# AnalogPart.net
KiCad netlist of a schematic drawn in Altium Designer
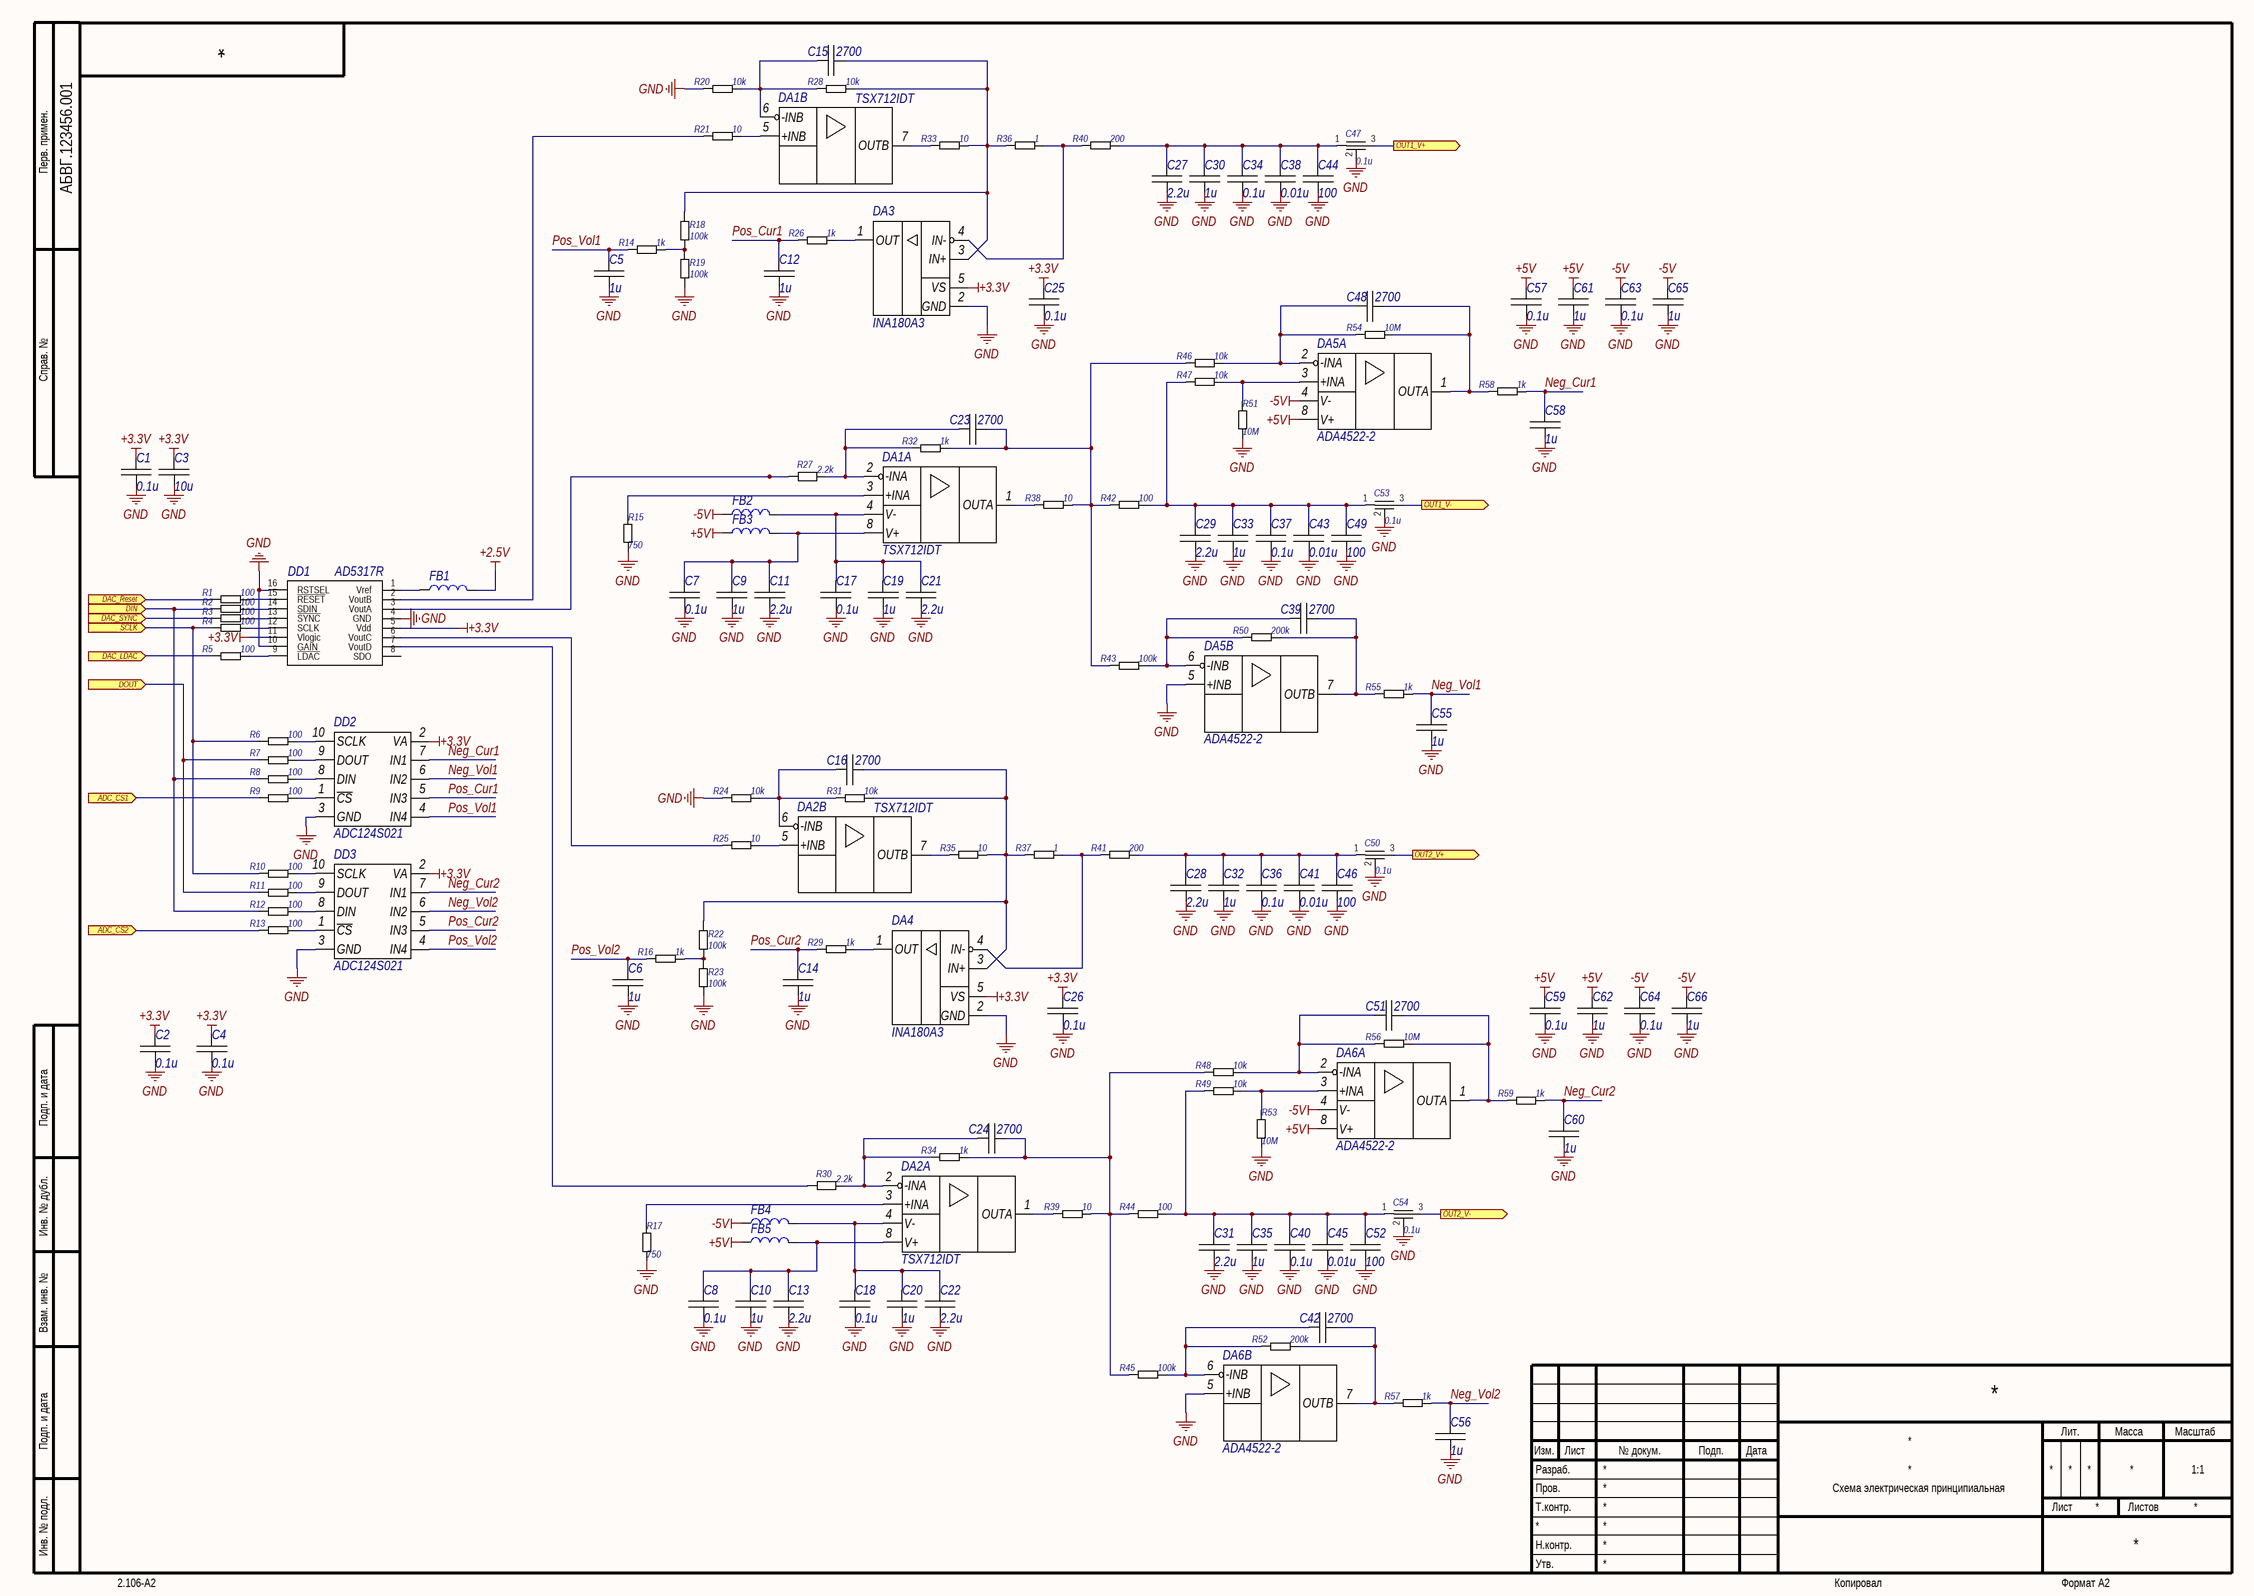
[diagram p0: AnalogPart.SchDoc]

(export (version "E")
  (design (tool "Eeschema 10.0.6"))
  (components
    (comp (ref "C1")
      (value "0.1u")
      (footprint "C0603")
      (libsource (lib "ComLib") (part "Capacitor Ceramic SMD"))
    )
    (comp (ref "C2")
      (value "0.1u")
      (footprint "C0603")
      (libsource (lib "ComLib") (part "Capacitor Ceramic SMD"))
    )
    (comp (ref "C3")
      (value "10u")
      (footprint "C0805")
      (libsource (lib "ComLib") (part "Capacitor Ceramic SMD"))
    )
    (comp (ref "C4")
      (value "0.1u")
      (footprint "C0603")
      (libsource (lib "ComLib") (part "Capacitor Ceramic SMD"))
    )
    (comp (ref "C5")
      (value "1u")
      (footprint "C0805")
      (libsource (lib "ComLib") (part "Capacitor Ceramic SMD"))
    )
    (comp (ref "C6")
      (value "1u")
      (footprint "C0805")
      (libsource (lib "ComLib") (part "Capacitor Ceramic SMD"))
    )
    (comp (ref "C7")
      (value "0.1u")
      (footprint "C0603")
      (libsource (lib "ComLib") (part "Capacitor Ceramic SMD"))
    )
    (comp (ref "C8")
      (value "0.1u")
      (footprint "C0603")
      (libsource (lib "ComLib") (part "Capacitor Ceramic SMD"))
    )
    (comp (ref "C9")
      (value "1u")
      (footprint "C0805")
      (libsource (lib "ComLib") (part "Capacitor Ceramic SMD"))
    )
    (comp (ref "C10")
      (value "1u")
      (footprint "C0805")
      (libsource (lib "ComLib") (part "Capacitor Ceramic SMD"))
    )
    (comp (ref "C11")
      (value "2.2u")
      (footprint "C0805")
      (libsource (lib "ComLib") (part "Capacitor Ceramic SMD"))
    )
    (comp (ref "C12")
      (value "1u")
      (footprint "C0805")
      (libsource (lib "ComLib") (part "Capacitor Ceramic SMD"))
    )
    (comp (ref "C13")
      (value "2.2u")
      (footprint "C0805")
      (libsource (lib "ComLib") (part "Capacitor Ceramic SMD"))
    )
    (comp (ref "C14")
      (value "1u")
      (footprint "C0805")
      (libsource (lib "ComLib") (part "Capacitor Ceramic SMD"))
    )
    (comp (ref "C15")
      (value "2700")
      (footprint "C0805")
      (libsource (lib "ComLib") (part "Capacitor Ceramic SMD"))
    )
    (comp (ref "C16")
      (value "2700")
      (footprint "C0805")
      (libsource (lib "ComLib") (part "Capacitor Ceramic SMD"))
    )
    (comp (ref "C17")
      (value "0.1u")
      (footprint "C0603")
      (libsource (lib "ComLib") (part "Capacitor Ceramic SMD"))
    )
    (comp (ref "C18")
      (value "0.1u")
      (footprint "C0603")
      (libsource (lib "ComLib") (part "Capacitor Ceramic SMD"))
    )
    (comp (ref "C19")
      (value "1u")
      (footprint "C0805")
      (libsource (lib "ComLib") (part "Capacitor Ceramic SMD"))
    )
    (comp (ref "C20")
      (value "1u")
      (footprint "C0805")
      (libsource (lib "ComLib") (part "Capacitor Ceramic SMD"))
    )
    (comp (ref "C21")
      (value "2.2u")
      (footprint "C0805")
      (libsource (lib "ComLib") (part "Capacitor Ceramic SMD"))
    )
    (comp (ref "C22")
      (value "2.2u")
      (footprint "C0805")
      (libsource (lib "ComLib") (part "Capacitor Ceramic SMD"))
    )
    (comp (ref "C23")
      (value "2700")
      (footprint "C0805")
      (libsource (lib "ComLib") (part "Capacitor Ceramic SMD"))
    )
    (comp (ref "C24")
      (value "2700")
      (footprint "C0805")
      (libsource (lib "ComLib") (part "Capacitor Ceramic SMD"))
    )
    (comp (ref "C25")
      (value "0.1u")
      (footprint "C0603")
      (libsource (lib "ComLib") (part "Capacitor Ceramic SMD"))
    )
    (comp (ref "C26")
      (value "0.1u")
      (footprint "C0603")
      (libsource (lib "ComLib") (part "Capacitor Ceramic SMD"))
    )
    (comp (ref "C27")
      (value "2.2u")
      (footprint "C0805")
      (libsource (lib "ComLib") (part "Capacitor Ceramic SMD"))
    )
    (comp (ref "C28")
      (value "2.2u")
      (footprint "C0805")
      (libsource (lib "ComLib") (part "Capacitor Ceramic SMD"))
    )
    (comp (ref "C29")
      (value "2.2u")
      (footprint "C0805")
      (libsource (lib "ComLib") (part "Capacitor Ceramic SMD"))
    )
    (comp (ref "C30")
      (value "1u")
      (footprint "C0805")
      (libsource (lib "ComLib") (part "Capacitor Ceramic SMD"))
    )
    (comp (ref "C31")
      (value "2.2u")
      (footprint "C0805")
      (libsource (lib "ComLib") (part "Capacitor Ceramic SMD"))
    )
    (comp (ref "C32")
      (value "1u")
      (footprint "C0805")
      (libsource (lib "ComLib") (part "Capacitor Ceramic SMD"))
    )
    (comp (ref "C33")
      (value "1u")
      (footprint "C0805")
      (libsource (lib "ComLib") (part "Capacitor Ceramic SMD"))
    )
    (comp (ref "C34")
      (value "0.1u")
      (footprint "C0805")
      (libsource (lib "ComLib") (part "Capacitor Ceramic SMD"))
    )
    (comp (ref "C35")
      (value "1u")
      (footprint "C0805")
      (libsource (lib "ComLib") (part "Capacitor Ceramic SMD"))
    )
    (comp (ref "C36")
      (value "0.1u")
      (footprint "C0805")
      (libsource (lib "ComLib") (part "Capacitor Ceramic SMD"))
    )
    (comp (ref "C37")
      (value "0.1u")
      (footprint "C0805")
      (libsource (lib "ComLib") (part "Capacitor Ceramic SMD"))
    )
    (comp (ref "C38")
      (value "0.01u")
      (footprint "C0805")
      (libsource (lib "ComLib") (part "Capacitor Ceramic SMD"))
    )
    (comp (ref "C39")
      (value "2700")
      (footprint "C0805")
      (libsource (lib "ComLib") (part "Capacitor Ceramic SMD"))
    )
    (comp (ref "C40")
      (value "0.1u")
      (footprint "C0805")
      (libsource (lib "ComLib") (part "Capacitor Ceramic SMD"))
    )
    (comp (ref "C41")
      (value "0.01u")
      (footprint "C0805")
      (libsource (lib "ComLib") (part "Capacitor Ceramic SMD"))
    )
    (comp (ref "C42")
      (value "2700")
      (footprint "C0805")
      (libsource (lib "ComLib") (part "Capacitor Ceramic SMD"))
    )
    (comp (ref "C43")
      (value "0.01u")
      (footprint "C0805")
      (libsource (lib "ComLib") (part "Capacitor Ceramic SMD"))
    )
    (comp (ref "C44")
      (value "100")
      (footprint "C0805")
      (libsource (lib "ComLib") (part "Capacitor Ceramic SMD"))
    )
    (comp (ref "C45")
      (value "0.01u")
      (footprint "C0805")
      (libsource (lib "ComLib") (part "Capacitor Ceramic SMD"))
    )
    (comp (ref "C46")
      (value "100")
      (footprint "C0805")
      (libsource (lib "ComLib") (part "Capacitor Ceramic SMD"))
    )
    (comp (ref "C47") (value "0.1u") (footprint "T0805") (libsource (lib "ComLib") (part "Cap 3 terminal")))
    (comp (ref "C48")
      (value "2700")
      (footprint "C0805")
      (libsource (lib "ComLib") (part "Capacitor Ceramic SMD"))
    )
    (comp (ref "C49")
      (value "100")
      (footprint "C0805")
      (libsource (lib "ComLib") (part "Capacitor Ceramic SMD"))
    )
    (comp (ref "C50") (value "0.1u") (footprint "T0805") (libsource (lib "ComLib") (part "Cap 3 terminal")))
    (comp (ref "C51")
      (value "2700")
      (footprint "C0805")
      (libsource (lib "ComLib") (part "Capacitor Ceramic SMD"))
    )
    (comp (ref "C52")
      (value "100")
      (footprint "C0805")
      (libsource (lib "ComLib") (part "Capacitor Ceramic SMD"))
    )
    (comp (ref "C53") (value "0.1u") (footprint "T0805") (libsource (lib "ComLib") (part "Cap 3 terminal")))
    (comp (ref "C54") (value "0.1u") (footprint "T0805") (libsource (lib "ComLib") (part "Cap 3 terminal")))
    (comp (ref "C55")
      (value "1u")
      (footprint "C0805")
      (libsource (lib "ComLib") (part "Capacitor Ceramic SMD"))
    )
    (comp (ref "C56")
      (value "1u")
      (footprint "C0805")
      (libsource (lib "ComLib") (part "Capacitor Ceramic SMD"))
    )
    (comp (ref "C57")
      (value "0.1u")
      (footprint "C0603")
      (libsource (lib "ComLib") (part "Capacitor Ceramic SMD"))
    )
    (comp (ref "C58")
      (value "1u")
      (footprint "C0805")
      (libsource (lib "ComLib") (part "Capacitor Ceramic SMD"))
    )
    (comp (ref "C59")
      (value "0.1u")
      (footprint "C0603")
      (libsource (lib "ComLib") (part "Capacitor Ceramic SMD"))
    )
    (comp (ref "C60")
      (value "1u")
      (footprint "C0805")
      (libsource (lib "ComLib") (part "Capacitor Ceramic SMD"))
    )
    (comp (ref "C61")
      (value "1u")
      (footprint "C0805")
      (libsource (lib "ComLib") (part "Capacitor Ceramic SMD"))
    )
    (comp (ref "C62")
      (value "1u")
      (footprint "C0805")
      (libsource (lib "ComLib") (part "Capacitor Ceramic SMD"))
    )
    (comp (ref "C63")
      (value "0.1u")
      (footprint "C0603")
      (libsource (lib "ComLib") (part "Capacitor Ceramic SMD"))
    )
    (comp (ref "C64")
      (value "0.1u")
      (footprint "C0603")
      (libsource (lib "ComLib") (part "Capacitor Ceramic SMD"))
    )
    (comp (ref "C65")
      (value "1u")
      (footprint "C0805")
      (libsource (lib "ComLib") (part "Capacitor Ceramic SMD"))
    )
    (comp (ref "C66")
      (value "1u")
      (footprint "C0805")
      (libsource (lib "ComLib") (part "Capacitor Ceramic SMD"))
    )
    (comp (ref "DA1") (value "TSX712IDT") (footprint "SOIC-8") (libsource (lib "ComLib") (part "ADA4522-2")))
    (comp (ref "DA2") (value "TSX712IDT") (footprint "SOIC-8") (libsource (lib "ComLib") (part "ADA4522-2")))
    (comp (ref "DA3") (value "INA180A3") (footprint "SOT23-5") (libsource (lib "ComLib") (part "INA180Ax")))
    (comp (ref "DA4") (value "INA180A3") (footprint "SOT23-5") (libsource (lib "ComLib") (part "INA180Ax")))
    (comp (ref "DA5") (value "ADA4522-2") (footprint "TSSOP-8") (libsource (lib "ComLib") (part "ADA4522-2")))
    (comp (ref "DA6") (value "ADA4522-2") (footprint "TSSOP-8") (libsource (lib "ComLib") (part "ADA4522-2")))
    (comp (ref "DD1") (value "AD5317R") (footprint "TSSOP-16") (libsource (lib "ComLib") (part "AD5317R")))
    (comp (ref "DD2")
      (value "ADC124S021")
      (footprint "VSSOP-10")
      (libsource (lib "ComLib") (part "ADC124S021"))
    )
    (comp (ref "DD3")
      (value "ADC124S021")
      (footprint "VSSOP-10")
      (libsource (lib "ComLib") (part "ADC124S021"))
    )
    (comp (ref "FB1")
      (value "MH1608-601Y")
      (footprint "L0603")
      (libsource (lib "ComLib") (part "Ferrite Bead"))
    )
    (comp (ref "FB2")
      (value "MH1608-601Y")
      (footprint "L0603")
      (libsource (lib "ComLib") (part "Ferrite Bead"))
    )
    (comp (ref "FB3")
      (value "MH1608-601Y")
      (footprint "L0603")
      (libsource (lib "ComLib") (part "Ferrite Bead"))
    )
    (comp (ref "FB4")
      (value "MH1608-601Y")
      (footprint "L0603")
      (libsource (lib "ComLib") (part "Ferrite Bead"))
    )
    (comp (ref "FB5")
      (value "MH1608-601Y")
      (footprint "L0603")
      (libsource (lib "ComLib") (part "Ferrite Bead"))
    )
    (comp (ref "R1") (value "100") (footprint "CR0603") (libsource (lib "ComLib") (part "Resistor SMD")))
    (comp (ref "R2") (value "100") (footprint "CR0603") (libsource (lib "ComLib") (part "Resistor SMD")))
    (comp (ref "R3") (value "100") (footprint "CR0603") (libsource (lib "ComLib") (part "Resistor SMD")))
    (comp (ref "R4") (value "100") (footprint "CR0603") (libsource (lib "ComLib") (part "Resistor SMD")))
    (comp (ref "R5") (value "100") (footprint "CR0603") (libsource (lib "ComLib") (part "Resistor SMD")))
    (comp (ref "R6") (value "100") (footprint "CR0603") (libsource (lib "ComLib") (part "Resistor SMD")))
    (comp (ref "R7") (value "100") (footprint "CR0603") (libsource (lib "ComLib") (part "Resistor SMD")))
    (comp (ref "R8") (value "100") (footprint "CR0603") (libsource (lib "ComLib") (part "Resistor SMD")))
    (comp (ref "R9") (value "100") (footprint "CR0603") (libsource (lib "ComLib") (part "Resistor SMD")))
    (comp (ref "R10") (value "100") (footprint "CR0603") (libsource (lib "ComLib") (part "Resistor SMD")))
    (comp (ref "R11") (value "100") (footprint "CR0603") (libsource (lib "ComLib") (part "Resistor SMD")))
    (comp (ref "R12") (value "100") (footprint "CR0603") (libsource (lib "ComLib") (part "Resistor SMD")))
    (comp (ref "R13") (value "100") (footprint "CR0603") (libsource (lib "ComLib") (part "Resistor SMD")))
    (comp (ref "R14") (value "1k") (footprint "CR0805") (libsource (lib "ComLib") (part "Resistor SMD")))
    (comp (ref "R15") (value "750") (footprint "CR0805") (libsource (lib "ComLib") (part "Resistor SMD")))
    (comp (ref "R16") (value "1k") (footprint "CR0805") (libsource (lib "ComLib") (part "Resistor SMD")))
    (comp (ref "R17") (value "750") (footprint "CR0805") (libsource (lib "ComLib") (part "Resistor SMD")))
    (comp (ref "R18") (value "100k") (footprint "CR0805") (libsource (lib "ComLib") (part "Resistor SMD")))
    (comp (ref "R19") (value "100k") (footprint "CR0805") (libsource (lib "ComLib") (part "Resistor SMD")))
    (comp (ref "R20") (value "10k") (footprint "CR0805") (libsource (lib "ComLib") (part "Resistor SMD")))
    (comp (ref "R21") (value "10") (footprint "CR0805") (libsource (lib "ComLib") (part "Resistor SMD")))
    (comp (ref "R22") (value "100k") (footprint "CR0805") (libsource (lib "ComLib") (part "Resistor SMD")))
    (comp (ref "R23") (value "100k") (footprint "CR0805") (libsource (lib "ComLib") (part "Resistor SMD")))
    (comp (ref "R24") (value "10k") (footprint "CR0805") (libsource (lib "ComLib") (part "Resistor SMD")))
    (comp (ref "R25") (value "10") (footprint "CR0805") (libsource (lib "ComLib") (part "Resistor SMD")))
    (comp (ref "R26") (value "1k") (footprint "CR0805") (libsource (lib "ComLib") (part "Resistor SMD")))
    (comp (ref "R27") (value "2.2k") (footprint "CR0805") (libsource (lib "ComLib") (part "Resistor SMD")))
    (comp (ref "R28") (value "10k") (footprint "CR0805") (libsource (lib "ComLib") (part "Resistor SMD")))
    (comp (ref "R29") (value "1k") (footprint "CR0805") (libsource (lib "ComLib") (part "Resistor SMD")))
    (comp (ref "R30") (value "2.2k") (footprint "CR0805") (libsource (lib "ComLib") (part "Resistor SMD")))
    (comp (ref "R31") (value "10k") (footprint "CR0805") (libsource (lib "ComLib") (part "Resistor SMD")))
    (comp (ref "R32") (value "1k") (footprint "CR0805") (libsource (lib "ComLib") (part "Resistor SMD")))
    (comp (ref "R33") (value "10") (footprint "CR0805") (libsource (lib "ComLib") (part "Resistor SMD")))
    (comp (ref "R34") (value "1k") (footprint "CR0805") (libsource (lib "ComLib") (part "Resistor SMD")))
    (comp (ref "R35") (value "10") (footprint "CR0805") (libsource (lib "ComLib") (part "Resistor SMD")))
    (comp (ref "R36") (value "1") (footprint "CR0805") (libsource (lib "ComLib") (part "Resistor SMD")))
    (comp (ref "R37") (value "1") (footprint "CR0805") (libsource (lib "ComLib") (part "Resistor SMD")))
    (comp (ref "R38") (value "10") (footprint "CR0805") (libsource (lib "ComLib") (part "Resistor SMD")))
    (comp (ref "R39") (value "10") (footprint "CR0805") (libsource (lib "ComLib") (part "Resistor SMD")))
    (comp (ref "R40") (value "200") (footprint "CR0805") (libsource (lib "ComLib") (part "Resistor SMD")))
    (comp (ref "R41") (value "200") (footprint "CR0805") (libsource (lib "ComLib") (part "Resistor SMD")))
    (comp (ref "R42") (value "100") (footprint "CR0805") (libsource (lib "ComLib") (part "Resistor SMD")))
    (comp (ref "R43") (value "100k") (footprint "CR0805") (libsource (lib "ComLib") (part "Resistor SMD")))
    (comp (ref "R44") (value "100") (footprint "CR0805") (libsource (lib "ComLib") (part "Resistor SMD")))
    (comp (ref "R45") (value "100k") (footprint "CR0805") (libsource (lib "ComLib") (part "Resistor SMD")))
    (comp (ref "R46") (value "10k") (footprint "CR0805") (libsource (lib "ComLib") (part "Resistor SMD")))
    (comp (ref "R47") (value "10k") (footprint "CR0805") (libsource (lib "ComLib") (part "Resistor SMD")))
    (comp (ref "R48") (value "10k") (footprint "CR0805") (libsource (lib "ComLib") (part "Resistor SMD")))
    (comp (ref "R49") (value "10k") (footprint "CR0805") (libsource (lib "ComLib") (part "Resistor SMD")))
    (comp (ref "R50") (value "200k") (footprint "CR0805") (libsource (lib "ComLib") (part "Resistor SMD")))
    (comp (ref "R51") (value "10M") (footprint "CR0805") (libsource (lib "ComLib") (part "Resistor SMD")))
    (comp (ref "R52") (value "200k") (footprint "CR0805") (libsource (lib "ComLib") (part "Resistor SMD")))
    (comp (ref "R53") (value "10M") (footprint "CR0805") (libsource (lib "ComLib") (part "Resistor SMD")))
    (comp (ref "R54") (value "10M") (footprint "CR0805") (libsource (lib "ComLib") (part "Resistor SMD")))
    (comp (ref "R55") (value "1k") (footprint "CR0805") (libsource (lib "ComLib") (part "Resistor SMD")))
    (comp (ref "R56") (value "10M") (footprint "CR0805") (libsource (lib "ComLib") (part "Resistor SMD")))
    (comp (ref "R57") (value "1k") (footprint "CR0805") (libsource (lib "ComLib") (part "Resistor SMD")))
    (comp (ref "R58") (value "1k") (footprint "CR0805") (libsource (lib "ComLib") (part "Resistor SMD")))
    (comp (ref "R59") (value "1k") (footprint "CR0805") (libsource (lib "ComLib") (part "Resistor SMD")))
  )
  (nets
    (net (code "1") (name "+2.5V") (class "Default")
      (node (ref "FB1") (pin "2") (pinfunction "2_2") (pintype "passive"))
    )
    (net (code "2") (name "+3.3V") (class "Default")
      (node (ref "C1") (pin "1") (pinfunction "1_1") (pintype "passive"))
      (node (ref "C2") (pin "1") (pinfunction "1_1") (pintype "passive"))
      (node (ref "C25") (pin "1") (pinfunction "1_1") (pintype "passive"))
      (node (ref "C26") (pin "1") (pinfunction "1_1") (pintype "passive"))
      (node (ref "C3") (pin "1") (pinfunction "1_1") (pintype "passive"))
      (node (ref "C4") (pin "1") (pinfunction "1_1") (pintype "passive"))
      (node (ref "DA3") (pin "5") (pinfunction "VS_5") (pintype "passive"))
      (node (ref "DA4") (pin "5") (pinfunction "VS_5") (pintype "passive"))
      (node (ref "DD1") (pin "11") (pinfunction "Vlogic_11") (pintype "passive"))
      (node (ref "DD1") (pin "5") (pinfunction "Vdd_5") (pintype "passive"))
      (node (ref "DD2") (pin "2") (pinfunction "VA_2") (pintype "passive"))
      (node (ref "DD3") (pin "2") (pinfunction "VA_2") (pintype "passive"))
    )
    (net (code "3") (name "+5V") (class "Default")
      (node (ref "C57") (pin "1") (pinfunction "1_1") (pintype "passive"))
      (node (ref "C59") (pin "1") (pinfunction "1_1") (pintype "passive"))
      (node (ref "C61") (pin "1") (pinfunction "1_1") (pintype "passive"))
      (node (ref "C62") (pin "1") (pinfunction "1_1") (pintype "passive"))
      (node (ref "DA5") (pin "8") (pinfunction "V+_8") (pintype "passive"))
      (node (ref "DA6") (pin "8") (pinfunction "V+_8") (pintype "passive"))
      (node (ref "FB3") (pin "1") (pinfunction "1_1") (pintype "passive"))
      (node (ref "FB5") (pin "1") (pinfunction "1_1") (pintype "passive"))
    )
    (net (code "4") (name "-5V") (class "Default")
      (node (ref "C63") (pin "1") (pinfunction "1_1") (pintype "passive"))
      (node (ref "C64") (pin "1") (pinfunction "1_1") (pintype "passive"))
      (node (ref "C65") (pin "1") (pinfunction "1_1") (pintype "passive"))
      (node (ref "C66") (pin "1") (pinfunction "1_1") (pintype "passive"))
      (node (ref "DA5") (pin "4") (pinfunction "V-_4") (pintype "passive"))
      (node (ref "DA6") (pin "4") (pinfunction "V-_4") (pintype "passive"))
      (node (ref "FB2") (pin "1") (pinfunction "1_1") (pintype "passive"))
      (node (ref "FB4") (pin "1") (pinfunction "1_1") (pintype "passive"))
    )
    (net (code "5") (name "/ADC_CS1") (class "Default") (node (ref "R9") (pin "1") (pintype "passive")))
    (net (code "6") (name "/ADC_CS2") (class "Default") (node (ref "R13") (pin "1") (pintype "passive")))
    (net (code "7") (name "/DAC_LDAC") (class "Default") (node (ref "R5") (pin "1") (pintype "passive")))
    (net (code "8") (name "/DAC_Reset") (class "Default") (node (ref "R1") (pin "1") (pintype "passive")))
    (net (code "9") (name "/DAC_SYNC") (class "Default") (node (ref "R3") (pin "1") (pintype "passive")))
    (net (code "10") (name "/DIN") (class "Default")
      (node (ref "R12") (pin "1") (pintype "passive"))
      (node (ref "R2") (pin "1") (pintype "passive"))
      (node (ref "R8") (pin "1") (pintype "passive"))
    )
    (net (code "11") (name "/DOUT") (class "Default")
      (node (ref "R11") (pin "1") (pintype "passive"))
      (node (ref "R7") (pin "1") (pintype "passive"))
    )
    (net (code "12") (name "/Neg_Cur1") (class "Default")
      (node (ref "C58") (pin "1") (pinfunction "1_1") (pintype "passive"))
      (node (ref "DD2") (pin "7") (pinfunction "IN1_7") (pintype "passive"))
      (node (ref "R58") (pin "2") (pintype "passive"))
    )
    (net (code "13") (name "/Neg_Cur2") (class "Default")
      (node (ref "C60") (pin "1") (pinfunction "1_1") (pintype "passive"))
      (node (ref "DD3") (pin "7") (pinfunction "IN1_7") (pintype "passive"))
      (node (ref "R59") (pin "2") (pintype "passive"))
    )
    (net (code "14") (name "/Neg_Vol1") (class "Default")
      (node (ref "C55") (pin "1") (pinfunction "1_1") (pintype "passive"))
      (node (ref "DD2") (pin "6") (pinfunction "IN2_6") (pintype "passive"))
      (node (ref "R55") (pin "2") (pintype "passive"))
    )
    (net (code "15") (name "/Neg_Vol2") (class "Default")
      (node (ref "C56") (pin "1") (pinfunction "1_1") (pintype "passive"))
      (node (ref "DD3") (pin "6") (pinfunction "IN2_6") (pintype "passive"))
      (node (ref "R57") (pin "2") (pintype "passive"))
    )
    (net (code "16") (name "/OUT1_V+") (class "Default")
      (node (ref "C47") (pin "3") (pinfunction "3_3") (pintype "passive"))
    )
    (net (code "17") (name "/OUT1_V-") (class "Default")
      (node (ref "C53") (pin "3") (pinfunction "3_3") (pintype "passive"))
    )
    (net (code "18") (name "/OUT2_V+") (class "Default")
      (node (ref "C50") (pin "3") (pinfunction "3_3") (pintype "passive"))
    )
    (net (code "19") (name "/OUT2_V-") (class "Default")
      (node (ref "C54") (pin "3") (pinfunction "3_3") (pintype "passive"))
    )
    (net (code "20") (name "/Pos_Cur1") (class "Default")
      (node (ref "C12") (pin "1") (pinfunction "1_1") (pintype "passive"))
      (node (ref "DD2") (pin "5") (pinfunction "IN3_5") (pintype "passive"))
      (node (ref "R26") (pin "1") (pintype "passive"))
    )
    (net (code "21") (name "/Pos_Cur2") (class "Default")
      (node (ref "C14") (pin "1") (pinfunction "1_1") (pintype "passive"))
      (node (ref "DD3") (pin "5") (pinfunction "IN3_5") (pintype "passive"))
      (node (ref "R29") (pin "1") (pintype "passive"))
    )
    (net (code "22") (name "/Pos_Vol1") (class "Default")
      (node (ref "C5") (pin "1") (pinfunction "1_1") (pintype "passive"))
      (node (ref "DD2") (pin "4") (pinfunction "IN4_4") (pintype "passive"))
      (node (ref "R14") (pin "1") (pintype "passive"))
    )
    (net (code "23") (name "/Pos_Vol2") (class "Default")
      (node (ref "C6") (pin "1") (pinfunction "1_1") (pintype "passive"))
      (node (ref "DD3") (pin "4") (pinfunction "IN4_4") (pintype "passive"))
      (node (ref "R16") (pin "1") (pintype "passive"))
    )
    (net (code "24") (name "/SCLK") (class "Default")
      (node (ref "R10") (pin "1") (pintype "passive"))
      (node (ref "R4") (pin "1") (pintype "passive"))
      (node (ref "R6") (pin "1") (pintype "passive"))
    )
    (net (code "25") (name "GND") (class "Default")
      (node (ref "C1") (pin "2") (pinfunction "2_2") (pintype "passive"))
      (node (ref "C10") (pin "2") (pinfunction "2_2") (pintype "passive"))
      (node (ref "C11") (pin "2") (pinfunction "2_2") (pintype "passive"))
      (node (ref "C12") (pin "2") (pinfunction "2_2") (pintype "passive"))
      (node (ref "C13") (pin "2") (pinfunction "2_2") (pintype "passive"))
      (node (ref "C14") (pin "2") (pinfunction "2_2") (pintype "passive"))
      (node (ref "C17") (pin "2") (pinfunction "2_2") (pintype "passive"))
      (node (ref "C18") (pin "2") (pinfunction "2_2") (pintype "passive"))
      (node (ref "C19") (pin "2") (pinfunction "2_2") (pintype "passive"))
      (node (ref "C2") (pin "2") (pinfunction "2_2") (pintype "passive"))
      (node (ref "C20") (pin "2") (pinfunction "2_2") (pintype "passive"))
      (node (ref "C21") (pin "2") (pinfunction "2_2") (pintype "passive"))
      (node (ref "C22") (pin "2") (pinfunction "2_2") (pintype "passive"))
      (node (ref "C25") (pin "2") (pinfunction "2_2") (pintype "passive"))
      (node (ref "C26") (pin "2") (pinfunction "2_2") (pintype "passive"))
      (node (ref "C27") (pin "2") (pinfunction "2_2") (pintype "passive"))
      (node (ref "C28") (pin "2") (pinfunction "2_2") (pintype "passive"))
      (node (ref "C29") (pin "2") (pinfunction "2_2") (pintype "passive"))
      (node (ref "C3") (pin "2") (pinfunction "2_2") (pintype "passive"))
      (node (ref "C30") (pin "2") (pinfunction "2_2") (pintype "passive"))
      (node (ref "C31") (pin "2") (pinfunction "2_2") (pintype "passive"))
      (node (ref "C32") (pin "2") (pinfunction "2_2") (pintype "passive"))
      (node (ref "C33") (pin "2") (pinfunction "2_2") (pintype "passive"))
      (node (ref "C34") (pin "2") (pinfunction "2_2") (pintype "passive"))
      (node (ref "C35") (pin "2") (pinfunction "2_2") (pintype "passive"))
      (node (ref "C36") (pin "2") (pinfunction "2_2") (pintype "passive"))
      (node (ref "C37") (pin "2") (pinfunction "2_2") (pintype "passive"))
      (node (ref "C38") (pin "2") (pinfunction "2_2") (pintype "passive"))
      (node (ref "C4") (pin "2") (pinfunction "2_2") (pintype "passive"))
      (node (ref "C40") (pin "2") (pinfunction "2_2") (pintype "passive"))
      (node (ref "C41") (pin "2") (pinfunction "2_2") (pintype "passive"))
      (node (ref "C43") (pin "2") (pinfunction "2_2") (pintype "passive"))
      (node (ref "C44") (pin "2") (pinfunction "2_2") (pintype "passive"))
      (node (ref "C45") (pin "2") (pinfunction "2_2") (pintype "passive"))
      (node (ref "C46") (pin "2") (pinfunction "2_2") (pintype "passive"))
      (node (ref "C47") (pin "2") (pinfunction "2_2") (pintype "passive"))
      (node (ref "C49") (pin "2") (pinfunction "2_2") (pintype "passive"))
      (node (ref "C5") (pin "2") (pinfunction "2_2") (pintype "passive"))
      (node (ref "C50") (pin "2") (pinfunction "2_2") (pintype "passive"))
      (node (ref "C52") (pin "2") (pinfunction "2_2") (pintype "passive"))
      (node (ref "C53") (pin "2") (pinfunction "2_2") (pintype "passive"))
      (node (ref "C54") (pin "2") (pinfunction "2_2") (pintype "passive"))
      (node (ref "C55") (pin "2") (pinfunction "2_2") (pintype "passive"))
      (node (ref "C56") (pin "2") (pinfunction "2_2") (pintype "passive"))
      (node (ref "C57") (pin "2") (pinfunction "2_2") (pintype "passive"))
      (node (ref "C58") (pin "2") (pinfunction "2_2") (pintype "passive"))
      (node (ref "C59") (pin "2") (pinfunction "2_2") (pintype "passive"))
      (node (ref "C6") (pin "2") (pinfunction "2_2") (pintype "passive"))
      (node (ref "C60") (pin "2") (pinfunction "2_2") (pintype "passive"))
      (node (ref "C61") (pin "2") (pinfunction "2_2") (pintype "passive"))
      (node (ref "C62") (pin "2") (pinfunction "2_2") (pintype "passive"))
      (node (ref "C63") (pin "2") (pinfunction "2_2") (pintype "passive"))
      (node (ref "C64") (pin "2") (pinfunction "2_2") (pintype "passive"))
      (node (ref "C65") (pin "2") (pinfunction "2_2") (pintype "passive"))
      (node (ref "C66") (pin "2") (pinfunction "2_2") (pintype "passive"))
      (node (ref "C7") (pin "2") (pinfunction "2_2") (pintype "passive"))
      (node (ref "C8") (pin "2") (pinfunction "2_2") (pintype "passive"))
      (node (ref "C9") (pin "2") (pinfunction "2_2") (pintype "passive"))
      (node (ref "DA3") (pin "2") (pinfunction "GND_2") (pintype "passive"))
      (node (ref "DA4") (pin "2") (pinfunction "GND_2") (pintype "passive"))
      (node (ref "DA5") (pin "5") (pinfunction "+INB_5") (pintype "passive"))
      (node (ref "DA6") (pin "5") (pinfunction "+INB_5") (pintype "passive"))
      (node (ref "DD1") (pin "10") (pinfunction "GAIN_10") (pintype "passive"))
      (node (ref "DD1") (pin "16") (pinfunction "RSTSEL_16") (pintype "passive"))
      (node (ref "DD1") (pin "4") (pinfunction "GND_4") (pintype "passive"))
      (node (ref "DD2") (pin "3") (pinfunction "GND_3") (pintype "passive"))
      (node (ref "DD3") (pin "3") (pinfunction "GND_3") (pintype "passive"))
      (node (ref "R15") (pin "1") (pintype "passive"))
      (node (ref "R17") (pin "1") (pintype "passive"))
      (node (ref "R19") (pin "2") (pintype "passive"))
      (node (ref "R20") (pin "2") (pintype "passive"))
      (node (ref "R23") (pin "2") (pintype "passive"))
      (node (ref "R24") (pin "2") (pintype "passive"))
      (node (ref "R51") (pin "1") (pintype "passive"))
      (node (ref "R53") (pin "1") (pintype "passive"))
    )
    (net (code "26") (name "Net-(C23-Pad2)") (class "Default")
      (node (ref "C23") (pin "2") (pinfunction "2_2") (pintype "passive"))
      (node (ref "R32") (pin "1") (pintype "passive"))
      (node (ref "R38") (pin "2") (pintype "passive"))
      (node (ref "R42") (pin "1") (pintype "passive"))
      (node (ref "R43") (pin "1") (pintype "passive"))
      (node (ref "R46") (pin "1") (pintype "passive"))
    )
    (net (code "27") (name "Net-(C24-Pad2)") (class "Default")
      (node (ref "C24") (pin "2") (pinfunction "2_2") (pintype "passive"))
      (node (ref "R34") (pin "1") (pintype "passive"))
      (node (ref "R39") (pin "2") (pintype "passive"))
      (node (ref "R44") (pin "1") (pintype "passive"))
      (node (ref "R45") (pin "1") (pintype "passive"))
      (node (ref "R48") (pin "1") (pintype "passive"))
    )
    (net (code "28") (name "Net-(C27-Pad1)") (class "Default")
      (node (ref "C27") (pin "1") (pinfunction "1_1") (pintype "passive"))
      (node (ref "C30") (pin "1") (pinfunction "1_1") (pintype "passive"))
      (node (ref "C34") (pin "1") (pinfunction "1_1") (pintype "passive"))
      (node (ref "C38") (pin "1") (pinfunction "1_1") (pintype "passive"))
      (node (ref "C44") (pin "1") (pinfunction "1_1") (pintype "passive"))
      (node (ref "C47") (pin "1") (pinfunction "1_1") (pintype "passive"))
      (node (ref "R40") (pin "2") (pintype "passive"))
    )
    (net (code "29") (name "Net-(C28-Pad1)") (class "Default")
      (node (ref "C28") (pin "1") (pinfunction "1_1") (pintype "passive"))
      (node (ref "C32") (pin "1") (pinfunction "1_1") (pintype "passive"))
      (node (ref "C36") (pin "1") (pinfunction "1_1") (pintype "passive"))
      (node (ref "C41") (pin "1") (pinfunction "1_1") (pintype "passive"))
      (node (ref "C46") (pin "1") (pinfunction "1_1") (pintype "passive"))
      (node (ref "C50") (pin "1") (pinfunction "1_1") (pintype "passive"))
      (node (ref "R41") (pin "2") (pintype "passive"))
    )
    (net (code "30") (name "Net-(C29-Pad1)") (class "Default")
      (node (ref "C29") (pin "1") (pinfunction "1_1") (pintype "passive"))
      (node (ref "C33") (pin "1") (pinfunction "1_1") (pintype "passive"))
      (node (ref "C37") (pin "1") (pinfunction "1_1") (pintype "passive"))
      (node (ref "C43") (pin "1") (pinfunction "1_1") (pintype "passive"))
      (node (ref "C49") (pin "1") (pinfunction "1_1") (pintype "passive"))
      (node (ref "C53") (pin "1") (pinfunction "1_1") (pintype "passive"))
      (node (ref "R42") (pin "2") (pintype "passive"))
      (node (ref "R47") (pin "1") (pintype "passive"))
    )
    (net (code "31") (name "Net-(C31-Pad1)") (class "Default")
      (node (ref "C31") (pin "1") (pinfunction "1_1") (pintype "passive"))
      (node (ref "C35") (pin "1") (pinfunction "1_1") (pintype "passive"))
      (node (ref "C40") (pin "1") (pinfunction "1_1") (pintype "passive"))
      (node (ref "C45") (pin "1") (pinfunction "1_1") (pintype "passive"))
      (node (ref "C52") (pin "1") (pinfunction "1_1") (pintype "passive"))
      (node (ref "C54") (pin "1") (pinfunction "1_1") (pintype "passive"))
      (node (ref "R44") (pin "2") (pintype "passive"))
      (node (ref "R49") (pin "1") (pintype "passive"))
    )
    (net (code "32") (name "Net-(DA1A-+INA)") (class "Default")
      (node (ref "DA1") (pin "3") (pinfunction "+INA_3") (pintype "passive"))
      (node (ref "R15") (pin "2") (pintype "passive"))
    )
    (net (code "33") (name "Net-(DA1A--INA)") (class "Default")
      (node (ref "C23") (pin "1") (pinfunction "1_1") (pintype "passive"))
      (node (ref "DA1") (pin "2") (pinfunction "-INA_2") (pintype "passive"))
      (node (ref "R27") (pin "1") (pintype "passive"))
      (node (ref "R32") (pin "2") (pintype "passive"))
    )
    (net (code "34") (name "Net-(DA1A-OUTA)") (class "Default")
      (node (ref "DA1") (pin "1") (pinfunction "OUTA_1") (pintype "passive"))
      (node (ref "R38") (pin "1") (pintype "passive"))
    )
    (net (code "35") (name "Net-(DA1A-V+)") (class "Default")
      (node (ref "C11") (pin "1") (pinfunction "1_1") (pintype "passive"))
      (node (ref "C7") (pin "1") (pinfunction "1_1") (pintype "passive"))
      (node (ref "C9") (pin "1") (pinfunction "1_1") (pintype "passive"))
      (node (ref "DA1") (pin "8") (pinfunction "V+_8") (pintype "passive"))
      (node (ref "FB3") (pin "2") (pinfunction "2_2") (pintype "passive"))
    )
    (net (code "36") (name "Net-(DA1A-V-)") (class "Default")
      (node (ref "C17") (pin "1") (pinfunction "1_1") (pintype "passive"))
      (node (ref "C19") (pin "1") (pinfunction "1_1") (pintype "passive"))
      (node (ref "C21") (pin "1") (pinfunction "1_1") (pintype "passive"))
      (node (ref "DA1") (pin "4") (pinfunction "V-_4") (pintype "passive"))
      (node (ref "FB2") (pin "2") (pinfunction "2_2") (pintype "passive"))
    )
    (net (code "37") (name "Net-(DA1B-+INB)") (class "Default")
      (node (ref "DA1") (pin "5") (pinfunction "+INB_5") (pintype "passive"))
      (node (ref "R21") (pin "1") (pintype "passive"))
    )
    (net (code "38") (name "Net-(DA1B--INB)") (class "Default")
      (node (ref "C15") (pin "1") (pinfunction "1_1") (pintype "passive"))
      (node (ref "DA1") (pin "6") (pinfunction "-INB_6") (pintype "passive"))
      (node (ref "R20") (pin "1") (pintype "passive"))
      (node (ref "R28") (pin "1") (pintype "passive"))
    )
    (net (code "39") (name "Net-(DA1B-OUTB)") (class "Default")
      (node (ref "DA1") (pin "7") (pinfunction "OUTB_7") (pintype "passive"))
      (node (ref "R33") (pin "1") (pintype "passive"))
    )
    (net (code "40") (name "Net-(DA2A-+INA)") (class "Default")
      (node (ref "DA2") (pin "3") (pinfunction "+INA_3") (pintype "passive"))
      (node (ref "R17") (pin "2") (pintype "passive"))
    )
    (net (code "41") (name "Net-(DA2A--INA)") (class "Default")
      (node (ref "C24") (pin "1") (pinfunction "1_1") (pintype "passive"))
      (node (ref "DA2") (pin "2") (pinfunction "-INA_2") (pintype "passive"))
      (node (ref "R30") (pin "1") (pintype "passive"))
      (node (ref "R34") (pin "2") (pintype "passive"))
    )
    (net (code "42") (name "Net-(DA2A-OUTA)") (class "Default")
      (node (ref "DA2") (pin "1") (pinfunction "OUTA_1") (pintype "passive"))
      (node (ref "R39") (pin "1") (pintype "passive"))
    )
    (net (code "43") (name "Net-(DA2A-V+)") (class "Default")
      (node (ref "C10") (pin "1") (pinfunction "1_1") (pintype "passive"))
      (node (ref "C13") (pin "1") (pinfunction "1_1") (pintype "passive"))
      (node (ref "C8") (pin "1") (pinfunction "1_1") (pintype "passive"))
      (node (ref "DA2") (pin "8") (pinfunction "V+_8") (pintype "passive"))
      (node (ref "FB5") (pin "2") (pinfunction "2_2") (pintype "passive"))
    )
    (net (code "44") (name "Net-(DA2A-V-)") (class "Default")
      (node (ref "C18") (pin "1") (pinfunction "1_1") (pintype "passive"))
      (node (ref "C20") (pin "1") (pinfunction "1_1") (pintype "passive"))
      (node (ref "C22") (pin "1") (pinfunction "1_1") (pintype "passive"))
      (node (ref "DA2") (pin "4") (pinfunction "V-_4") (pintype "passive"))
      (node (ref "FB4") (pin "2") (pinfunction "2_2") (pintype "passive"))
    )
    (net (code "45") (name "Net-(DA2B-+INB)") (class "Default")
      (node (ref "DA2") (pin "5") (pinfunction "+INB_5") (pintype "passive"))
      (node (ref "R25") (pin "1") (pintype "passive"))
    )
    (net (code "46") (name "Net-(DA2B--INB)") (class "Default")
      (node (ref "C16") (pin "1") (pinfunction "1_1") (pintype "passive"))
      (node (ref "DA2") (pin "6") (pinfunction "-INB_6") (pintype "passive"))
      (node (ref "R24") (pin "1") (pintype "passive"))
      (node (ref "R31") (pin "1") (pintype "passive"))
    )
    (net (code "47") (name "Net-(DA2B-OUTB)") (class "Default")
      (node (ref "DA2") (pin "7") (pinfunction "OUTB_7") (pintype "passive"))
      (node (ref "R35") (pin "1") (pintype "passive"))
    )
    (net (code "48") (name "Net-(DA3-IN+)") (class "Default")
      (node (ref "C15") (pin "2") (pinfunction "2_2") (pintype "passive"))
      (node (ref "DA3") (pin "3") (pinfunction "IN+_3") (pintype "passive"))
      (node (ref "R18") (pin "2") (pintype "passive"))
      (node (ref "R28") (pin "2") (pintype "passive"))
      (node (ref "R33") (pin "2") (pintype "passive"))
      (node (ref "R36") (pin "1") (pintype "passive"))
    )
    (net (code "49") (name "Net-(DA3-IN-)") (class "Default")
      (node (ref "DA3") (pin "4") (pinfunction "IN-_4") (pintype "passive"))
      (node (ref "R36") (pin "2") (pintype "passive"))
      (node (ref "R40") (pin "1") (pintype "passive"))
    )
    (net (code "50") (name "Net-(DA3-OUT)") (class "Default")
      (node (ref "DA3") (pin "1") (pinfunction "OUT_1") (pintype "passive"))
      (node (ref "R26") (pin "2") (pintype "passive"))
    )
    (net (code "51") (name "Net-(DA4-IN+)") (class "Default")
      (node (ref "C16") (pin "2") (pinfunction "2_2") (pintype "passive"))
      (node (ref "DA4") (pin "3") (pinfunction "IN+_3") (pintype "passive"))
      (node (ref "R22") (pin "2") (pintype "passive"))
      (node (ref "R31") (pin "2") (pintype "passive"))
      (node (ref "R35") (pin "2") (pintype "passive"))
      (node (ref "R37") (pin "1") (pintype "passive"))
    )
    (net (code "52") (name "Net-(DA4-IN-)") (class "Default")
      (node (ref "DA4") (pin "4") (pinfunction "IN-_4") (pintype "passive"))
      (node (ref "R37") (pin "2") (pintype "passive"))
      (node (ref "R41") (pin "1") (pintype "passive"))
    )
    (net (code "53") (name "Net-(DA4-OUT)") (class "Default")
      (node (ref "DA4") (pin "1") (pinfunction "OUT_1") (pintype "passive"))
      (node (ref "R29") (pin "2") (pintype "passive"))
    )
    (net (code "54") (name "Net-(DA5A-+INA)") (class "Default")
      (node (ref "DA5") (pin "3") (pinfunction "+INA_3") (pintype "passive"))
      (node (ref "R47") (pin "2") (pintype "passive"))
      (node (ref "R51") (pin "2") (pintype "passive"))
    )
    (net (code "55") (name "Net-(DA5A--INA)") (class "Default")
      (node (ref "C48") (pin "1") (pinfunction "1_1") (pintype "passive"))
      (node (ref "DA5") (pin "2") (pinfunction "-INA_2") (pintype "passive"))
      (node (ref "R46") (pin "2") (pintype "passive"))
      (node (ref "R54") (pin "1") (pintype "passive"))
    )
    (net (code "56") (name "Net-(DA5A-OUTA)") (class "Default")
      (node (ref "C48") (pin "2") (pinfunction "2_2") (pintype "passive"))
      (node (ref "DA5") (pin "1") (pinfunction "OUTA_1") (pintype "passive"))
      (node (ref "R54") (pin "2") (pintype "passive"))
      (node (ref "R58") (pin "1") (pintype "passive"))
    )
    (net (code "57") (name "Net-(DA5B--INB)") (class "Default")
      (node (ref "C39") (pin "1") (pinfunction "1_1") (pintype "passive"))
      (node (ref "DA5") (pin "6") (pinfunction "-INB_6") (pintype "passive"))
      (node (ref "R43") (pin "2") (pintype "passive"))
      (node (ref "R50") (pin "1") (pintype "passive"))
    )
    (net (code "58") (name "Net-(DA5B-OUTB)") (class "Default")
      (node (ref "C39") (pin "2") (pinfunction "2_2") (pintype "passive"))
      (node (ref "DA5") (pin "7") (pinfunction "OUTB_7") (pintype "passive"))
      (node (ref "R50") (pin "2") (pintype "passive"))
      (node (ref "R55") (pin "1") (pintype "passive"))
    )
    (net (code "59") (name "Net-(DA6A-+INA)") (class "Default")
      (node (ref "DA6") (pin "3") (pinfunction "+INA_3") (pintype "passive"))
      (node (ref "R49") (pin "2") (pintype "passive"))
      (node (ref "R53") (pin "2") (pintype "passive"))
    )
    (net (code "60") (name "Net-(DA6A--INA)") (class "Default")
      (node (ref "C51") (pin "1") (pinfunction "1_1") (pintype "passive"))
      (node (ref "DA6") (pin "2") (pinfunction "-INA_2") (pintype "passive"))
      (node (ref "R48") (pin "2") (pintype "passive"))
      (node (ref "R56") (pin "1") (pintype "passive"))
    )
    (net (code "61") (name "Net-(DA6A-OUTA)") (class "Default")
      (node (ref "C51") (pin "2") (pinfunction "2_2") (pintype "passive"))
      (node (ref "DA6") (pin "1") (pinfunction "OUTA_1") (pintype "passive"))
      (node (ref "R56") (pin "2") (pintype "passive"))
      (node (ref "R59") (pin "1") (pintype "passive"))
    )
    (net (code "62") (name "Net-(DA6B--INB)") (class "Default")
      (node (ref "C42") (pin "1") (pinfunction "1_1") (pintype "passive"))
      (node (ref "DA6") (pin "6") (pinfunction "-INB_6") (pintype "passive"))
      (node (ref "R45") (pin "2") (pintype "passive"))
      (node (ref "R52") (pin "1") (pintype "passive"))
    )
    (net (code "63") (name "Net-(DA6B-OUTB)") (class "Default")
      (node (ref "C42") (pin "2") (pinfunction "2_2") (pintype "passive"))
      (node (ref "DA6") (pin "7") (pinfunction "OUTB_7") (pintype "passive"))
      (node (ref "R52") (pin "2") (pintype "passive"))
      (node (ref "R57") (pin "1") (pintype "passive"))
    )
    (net (code "64") (name "Net-(DD1-SCLK)") (class "Default")
      (node (ref "DD1") (pin "12") (pinfunction "SCLK_12") (pintype "passive"))
      (node (ref "R4") (pin "2") (pintype "passive"))
    )
    (net (code "65") (name "Net-(DD1-SDIN)") (class "Default")
      (node (ref "DD1") (pin "14") (pinfunction "SDIN_14") (pintype "passive"))
      (node (ref "R2") (pin "2") (pintype "passive"))
    )
    (net (code "66") (name "Net-(DD1-VoutA)") (class "Default")
      (node (ref "DD1") (pin "3") (pinfunction "VoutA_3") (pintype "passive"))
      (node (ref "R27") (pin "2") (pintype "passive"))
    )
    (net (code "67") (name "Net-(DD1-VoutB)") (class "Default")
      (node (ref "DD1") (pin "2") (pinfunction "VoutB_2") (pintype "passive"))
      (node (ref "R21") (pin "2") (pintype "passive"))
    )
    (net (code "68") (name "Net-(DD1-VoutC)") (class "Default")
      (node (ref "DD1") (pin "6") (pinfunction "VoutC_6") (pintype "passive"))
      (node (ref "R25") (pin "2") (pintype "passive"))
    )
    (net (code "69") (name "Net-(DD1-VoutD)") (class "Default")
      (node (ref "DD1") (pin "7") (pinfunction "VoutD_7") (pintype "passive"))
      (node (ref "R30") (pin "2") (pintype "passive"))
    )
    (net (code "70") (name "Net-(DD1-Vref)") (class "Default")
      (node (ref "DD1") (pin "1") (pinfunction "Vref_1") (pintype "passive"))
      (node (ref "FB1") (pin "1") (pinfunction "1_1") (pintype "passive"))
    )
    (net (code "71") (name "Net-(DD1-~{LDAC})") (class "Default")
      (node (ref "DD1") (pin "9") (pinfunction "~{LDAC}_9") (pintype "passive"))
      (node (ref "R5") (pin "2") (pintype "passive"))
    )
    (net (code "72") (name "Net-(DD1-~{RESET})") (class "Default")
      (node (ref "DD1") (pin "15") (pinfunction "~{RESET}_15") (pintype "passive"))
      (node (ref "R1") (pin "2") (pintype "passive"))
    )
    (net (code "73") (name "Net-(DD1-~{SYNC})") (class "Default")
      (node (ref "DD1") (pin "13") (pinfunction "~{SYNC}_13") (pintype "passive"))
      (node (ref "R3") (pin "2") (pintype "passive"))
    )
    (net (code "74") (name "Net-(DD2-DIN)") (class "Default")
      (node (ref "DD2") (pin "8") (pinfunction "DIN_8") (pintype "passive"))
      (node (ref "R8") (pin "2") (pintype "passive"))
    )
    (net (code "75") (name "Net-(DD2-DOUT)") (class "Default")
      (node (ref "DD2") (pin "9") (pinfunction "DOUT_9") (pintype "passive"))
      (node (ref "R7") (pin "2") (pintype "passive"))
    )
    (net (code "76") (name "Net-(DD2-SCLK)") (class "Default")
      (node (ref "DD2") (pin "10") (pinfunction "SCLK_10") (pintype "passive"))
      (node (ref "R6") (pin "2") (pintype "passive"))
    )
    (net (code "77") (name "Net-(DD2-~{CS})") (class "Default")
      (node (ref "DD2") (pin "1") (pinfunction "~{CS}_1") (pintype "passive"))
      (node (ref "R9") (pin "2") (pintype "passive"))
    )
    (net (code "78") (name "Net-(DD3-DIN)") (class "Default")
      (node (ref "DD3") (pin "8") (pinfunction "DIN_8") (pintype "passive"))
      (node (ref "R12") (pin "2") (pintype "passive"))
    )
    (net (code "79") (name "Net-(DD3-DOUT)") (class "Default")
      (node (ref "DD3") (pin "9") (pinfunction "DOUT_9") (pintype "passive"))
      (node (ref "R11") (pin "2") (pintype "passive"))
    )
    (net (code "80") (name "Net-(DD3-SCLK)") (class "Default")
      (node (ref "DD3") (pin "10") (pinfunction "SCLK_10") (pintype "passive"))
      (node (ref "R10") (pin "2") (pintype "passive"))
    )
    (net (code "81") (name "Net-(DD3-~{CS})") (class "Default")
      (node (ref "DD3") (pin "1") (pinfunction "~{CS}_1") (pintype "passive"))
      (node (ref "R13") (pin "2") (pintype "passive"))
    )
    (net (code "82") (name "Net-(R14-Pad2)") (class "Default")
      (node (ref "R14") (pin "2") (pintype "passive"))
      (node (ref "R18") (pin "1") (pintype "passive"))
      (node (ref "R19") (pin "1") (pintype "passive"))
    )
    (net (code "83") (name "Net-(R16-Pad2)") (class "Default")
      (node (ref "R16") (pin "2") (pintype "passive"))
      (node (ref "R22") (pin "1") (pintype "passive"))
      (node (ref "R23") (pin "1") (pintype "passive"))
    )
    (net (code "84") (name "unconnected-(DD1-SDO-Pad8)") (class "Default")
      (node (ref "DD1") (pin "8") (pinfunction "SDO_8") (pintype "passive"))
    )
  )
)
